# eeZeeAmp.net
KiCad netlist of a schematic drawn in EAGLE
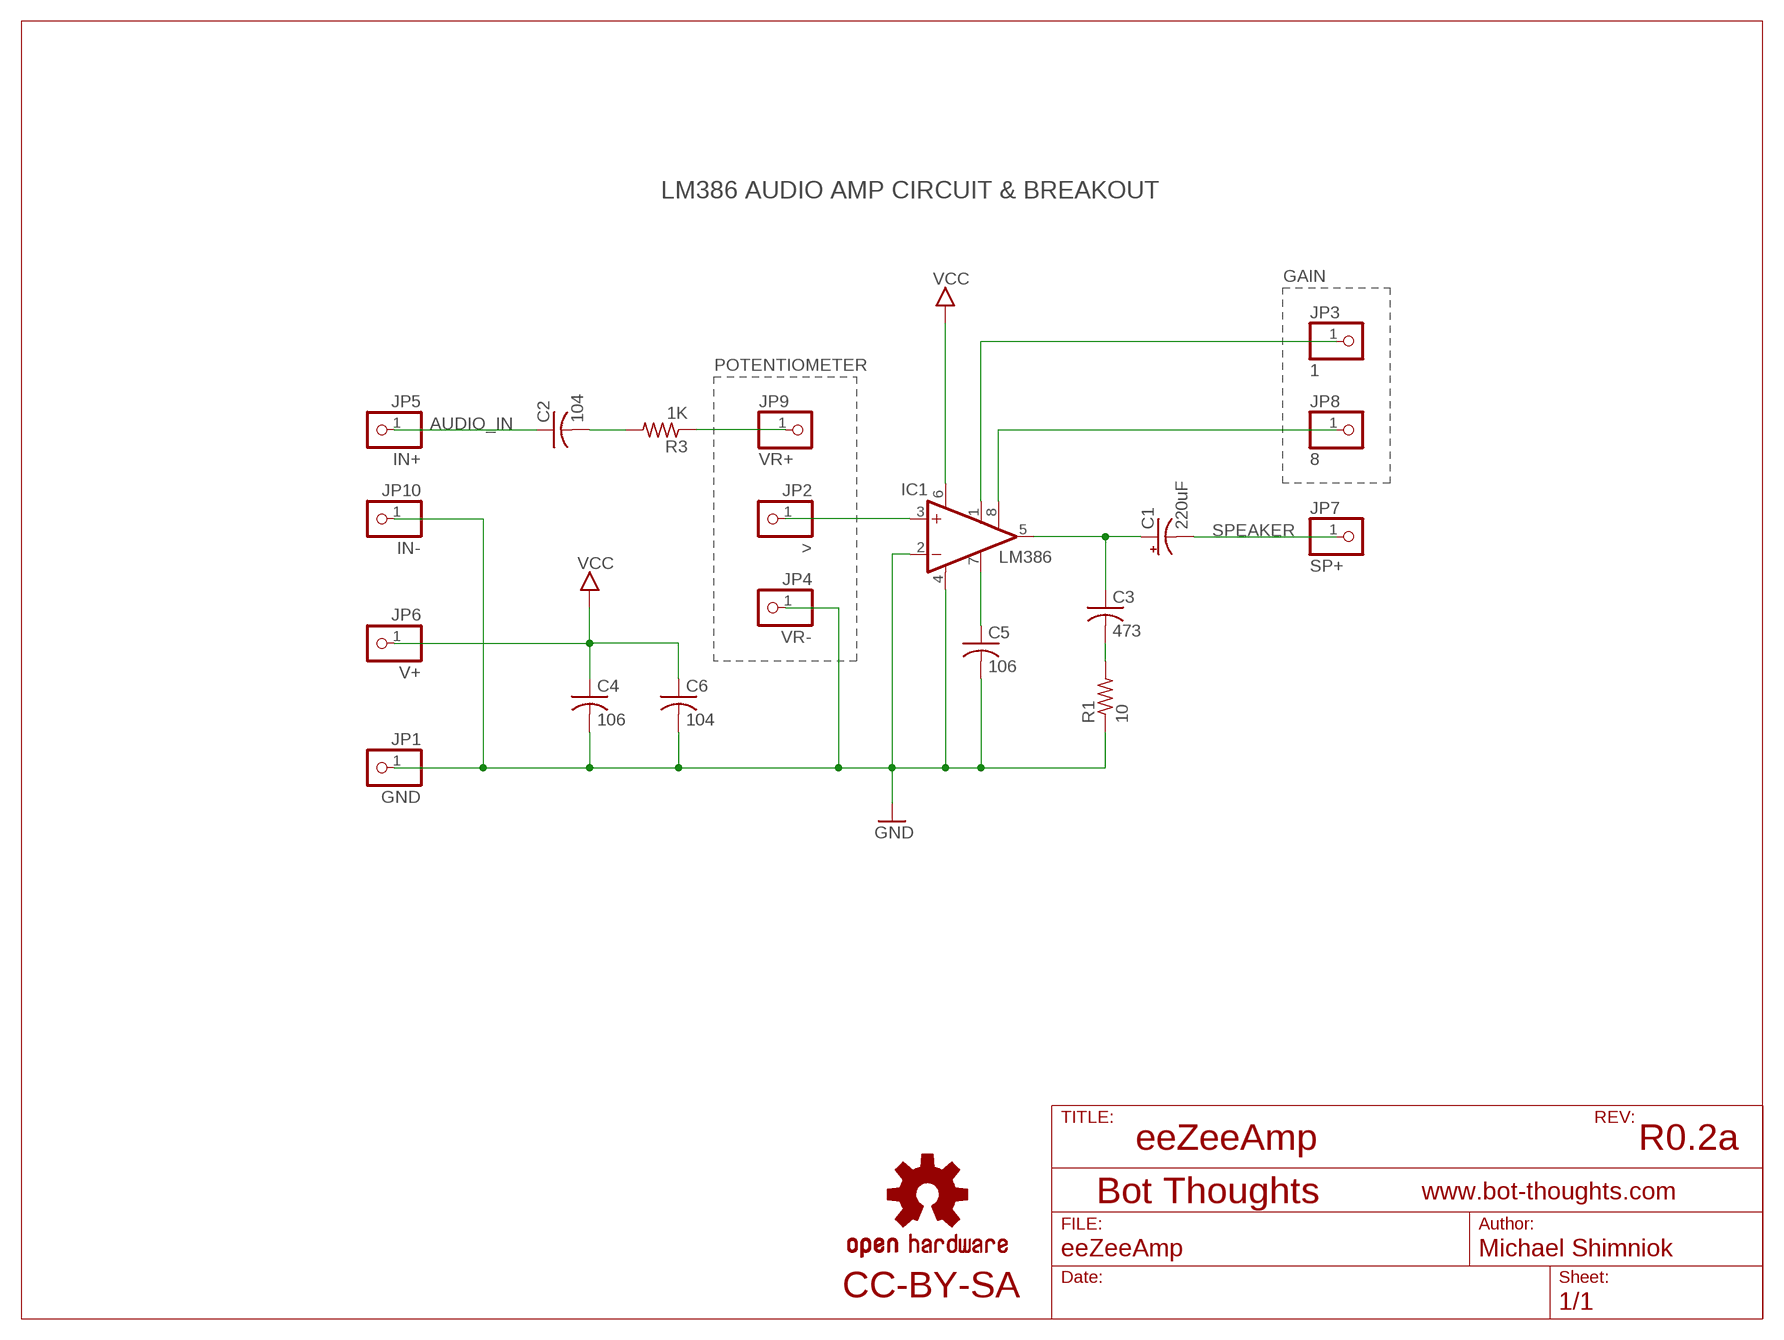
[diagram p0: schematic, sheet 1]

(export (version "E")
  (design (tool "Eeschema 10.0.6"))
  (components
    (comp (ref "C1")
      (value "220uF")
      (footprint "eagle-import:E3,5-8")
      (libsource (lib "eagle-import") (part "CPOL-USE3.5-8"))
    )
    (comp (ref "C2")
      (value "104")
      (footprint "eagle-import:C0603")
      (libsource (lib "eagle-import") (part "C-USC0603"))
    )
    (comp (ref "C3")
      (value "473")
      (footprint "eagle-import:C0603")
      (libsource (lib "eagle-import") (part "C-USC0603"))
    )
    (comp (ref "C4")
      (value "106")
      (footprint "eagle-import:C1206")
      (libsource (lib "eagle-import") (part "C-USC1206"))
    )
    (comp (ref "C5")
      (value "106")
      (footprint "eagle-import:C1206")
      (libsource (lib "eagle-import") (part "C-USC1206"))
    )
    (comp (ref "C6")
      (value "104")
      (footprint "eagle-import:C0603")
      (libsource (lib "eagle-import") (part "C-USC0603"))
    )
    (comp (ref "IC1")
      (value "LM386")
      (footprint "eagle-import:SO08")
      (libsource (lib "eagle-import") (part "LM386?-M1"))
    )
    (comp (ref "JP1")
      (value "GND")
      (footprint "eagle-import:1X01-S")
      (libsource (lib "eagle-import") (part "PINHD-1X01_2.54-S"))
    )
    (comp (ref "JP2")
      (value ">")
      (footprint "eagle-import:1X01-S")
      (libsource (lib "eagle-import") (part "PINHD-1X01_2.54-S"))
    )
    (comp (ref "JP3")
      (value "1")
      (footprint "eagle-import:1X01-S")
      (libsource (lib "eagle-import") (part "PINHD-1X01_2.54-S"))
    )
    (comp (ref "JP4")
      (value "VR-")
      (footprint "eagle-import:1X01-S")
      (libsource (lib "eagle-import") (part "PINHD-1X01_2.54-S"))
    )
    (comp (ref "JP5")
      (value "IN+")
      (footprint "eagle-import:1X01-S")
      (libsource (lib "eagle-import") (part "PINHD-1X01_2.54-S"))
    )
    (comp (ref "JP6")
      (value "V+")
      (footprint "eagle-import:1X01-S")
      (libsource (lib "eagle-import") (part "PINHD-1X01_2.54-S"))
    )
    (comp (ref "JP7")
      (value "SP+")
      (footprint "eagle-import:1X01-S")
      (libsource (lib "eagle-import") (part "PINHD-1X01_2.54-S"))
    )
    (comp (ref "JP8")
      (value "8")
      (footprint "eagle-import:1X01-S")
      (libsource (lib "eagle-import") (part "PINHD-1X01_2.54-S"))
    )
    (comp (ref "JP9")
      (value "VR+")
      (footprint "eagle-import:1X01-S")
      (libsource (lib "eagle-import") (part "PINHD-1X01_2.54-S"))
    )
    (comp (ref "JP10")
      (value "IN-")
      (footprint "eagle-import:1X01-S")
      (libsource (lib "eagle-import") (part "PINHD-1X01_2.54-S"))
    )
    (comp (ref "LOGO2")
      (value "OSHW-LOGOS")
      (footprint "eagle-import:OSHW-LOGO-S")
      (libsource (lib "eagle-import") (part "OSHW-LOGOS"))
    )
    (comp (ref "R1")
      (value "10")
      (footprint "eagle-import:R0603")
      (libsource (lib "eagle-import") (part "R-US_R0603"))
    )
    (comp (ref "R3")
      (value "1K")
      (footprint "eagle-import:R0603")
      (libsource (lib "eagle-import") (part "R-US_R0603"))
    )
  )
  (nets
    (net (code "1") (name "/AUDIO_IN") (class "Default")
      (node (ref "C2") (pin "1") (pinfunction "1_1") (pintype "passive"))
      (node (ref "JP5") (pin "1") (pinfunction "1_1") (pintype "passive"))
    )
    (net (code "2") (name "/SPEAKER") (class "Default")
      (node (ref "C1") (pin "-") (pinfunction "-_-") (pintype "passive"))
      (node (ref "JP7") (pin "1") (pinfunction "1_1") (pintype "passive"))
    )
    (net (code "3") (name "GND") (class "Default")
      (node (ref "C4") (pin "2") (pinfunction "2_2") (pintype "passive"))
      (node (ref "C5") (pin "2") (pinfunction "2_2") (pintype "passive"))
      (node (ref "C6") (pin "2") (pinfunction "2_2") (pintype "passive"))
      (node (ref "IC1") (pin "2") (pinfunction "-IN_2") (pintype "input"))
      (node (ref "IC1") (pin "4") (pinfunction "GND_4") (pintype "power_in"))
      (node (ref "JP1") (pin "1") (pinfunction "1_1") (pintype "passive"))
      (node (ref "JP10") (pin "1") (pinfunction "1_1") (pintype "passive"))
      (node (ref "JP4") (pin "1") (pinfunction "1_1") (pintype "passive"))
      (node (ref "R1") (pin "1") (pinfunction "1_1") (pintype "passive"))
    )
    (net (code "4") (name "Net-(C2-Pad2)") (class "Default")
      (node (ref "C2") (pin "2") (pinfunction "2_2") (pintype "passive"))
      (node (ref "R3") (pin "2") (pinfunction "2_2") (pintype "passive"))
    )
    (net (code "5") (name "Net-(C3-Pad2)") (class "Default")
      (node (ref "C3") (pin "2") (pinfunction "2_2") (pintype "passive"))
      (node (ref "R1") (pin "2") (pinfunction "2_2") (pintype "passive"))
    )
    (net (code "6") (name "Net-(IC1-+IN)") (class "Default")
      (node (ref "IC1") (pin "3") (pinfunction "+IN_3") (pintype "input"))
      (node (ref "JP2") (pin "1") (pinfunction "1_1") (pintype "passive"))
    )
    (net (code "7") (name "Net-(IC1-BYPASS)") (class "Default")
      (node (ref "C5") (pin "1") (pinfunction "1_1") (pintype "passive"))
      (node (ref "IC1") (pin "7") (pinfunction "BYPASS_7") (pintype "passive"))
    )
    (net (code "8") (name "Net-(IC1-GAIN-Pad1)") (class "Default")
      (node (ref "IC1") (pin "1") (pinfunction "GAIN_1") (pintype "passive"))
      (node (ref "JP3") (pin "1") (pinfunction "1_1") (pintype "passive"))
    )
    (net (code "9") (name "Net-(IC1-GAIN-Pad8)") (class "Default")
      (node (ref "IC1") (pin "8") (pinfunction "GAIN_8") (pintype "passive"))
      (node (ref "JP8") (pin "1") (pinfunction "1_1") (pintype "passive"))
    )
    (net (code "10") (name "Net-(IC1-OUT)") (class "Default")
      (node (ref "C1") (pin "+") (pinfunction "+_+") (pintype "passive"))
      (node (ref "C3") (pin "1") (pinfunction "1_1") (pintype "passive"))
      (node (ref "IC1") (pin "5") (pinfunction "OUT_5") (pintype "output"))
    )
    (net (code "11") (name "Net-(JP9-Pad1)") (class "Default")
      (node (ref "JP9") (pin "1") (pinfunction "1_1") (pintype "passive"))
      (node (ref "R3") (pin "1") (pinfunction "1_1") (pintype "passive"))
    )
    (net (code "12") (name "VCC") (class "Default")
      (node (ref "C4") (pin "1") (pinfunction "1_1") (pintype "passive"))
      (node (ref "C6") (pin "1") (pinfunction "1_1") (pintype "passive"))
      (node (ref "IC1") (pin "6") (pinfunction "VS_6") (pintype "power_in"))
      (node (ref "JP6") (pin "1") (pinfunction "1_1") (pintype "passive"))
    )
  )
)
